# sensor.net
KiCad netlist of a schematic drawn in EAGLE
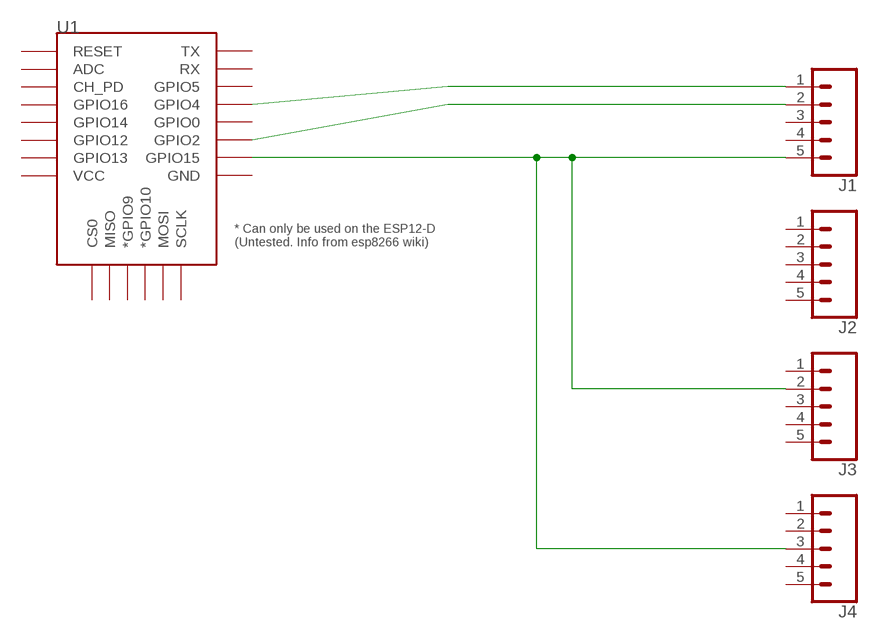
[diagram p0: schematic, sheet 1]

(export (version "E")
  (design (tool "Eeschema 10.0.6"))
  (components
    (comp (ref "J1")
      (value "CONN_05SMD")
      (footprint "eagle-import:1X05_1MM")
      (libsource (lib "eagle-import") (part "CONN_05SMD"))
    )
    (comp (ref "J2")
      (value "CONN_05SMD")
      (footprint "eagle-import:1X05_1MM")
      (libsource (lib "eagle-import") (part "CONN_05SMD"))
    )
    (comp (ref "J3")
      (value "CONN_05SMD")
      (footprint "eagle-import:1X05_1MM")
      (libsource (lib "eagle-import") (part "CONN_05SMD"))
    )
    (comp (ref "J4")
      (value "CONN_05SMD")
      (footprint "eagle-import:1X05_1MM")
      (libsource (lib "eagle-import") (part "CONN_05SMD"))
    )
    (comp (ref "U1")
      (value "ESP12ESMD")
      (footprint "eagle-import:ESP12E-SMD")
      (libsource (lib "eagle-import") (part "ESP12ESMD"))
    )
  )
  (nets
    (net (code "1") (name "Net-(J1-Pad1)") (class "Default")
      (node (ref "J1") (pin "1") (pinfunction "1_1") (pintype "passive"))
      (node (ref "U1") (pin "GPIO4") (pinfunction "GPIO4_GPIO4") (pintype "bidirectional"))
    )
    (net (code "2") (name "Net-(J1-Pad2)") (class "Default")
      (node (ref "J1") (pin "2") (pinfunction "2_2") (pintype "passive"))
      (node (ref "U1") (pin "GPIO2") (pinfunction "GPIO2_GPIO2") (pintype "bidirectional"))
    )
    (net (code "3") (name "Net-(J1-Pad5)") (class "Default")
      (node (ref "J1") (pin "5") (pinfunction "5_5") (pintype "passive"))
      (node (ref "J3") (pin "2") (pinfunction "2_2") (pintype "passive"))
      (node (ref "J4") (pin "3") (pinfunction "3_3") (pintype "passive"))
      (node (ref "U1") (pin "GPIO15") (pinfunction "GPIO15_GPIO15") (pintype "bidirectional"))
    )
    (net (code "4") (name "unconnected-(J1-Pad3)") (class "Default")
      (node (ref "J1") (pin "3") (pinfunction "3_3") (pintype "passive"))
    )
    (net (code "5") (name "unconnected-(J1-Pad4)") (class "Default")
      (node (ref "J1") (pin "4") (pinfunction "4_4") (pintype "passive"))
    )
    (net (code "6") (name "unconnected-(J2-Pad1)") (class "Default")
      (node (ref "J2") (pin "1") (pinfunction "1_1") (pintype "passive"))
    )
    (net (code "7") (name "unconnected-(J2-Pad2)") (class "Default")
      (node (ref "J2") (pin "2") (pinfunction "2_2") (pintype "passive"))
    )
    (net (code "8") (name "unconnected-(J2-Pad3)") (class "Default")
      (node (ref "J2") (pin "3") (pinfunction "3_3") (pintype "passive"))
    )
    (net (code "9") (name "unconnected-(J2-Pad4)") (class "Default")
      (node (ref "J2") (pin "4") (pinfunction "4_4") (pintype "passive"))
    )
    (net (code "10") (name "unconnected-(J2-Pad5)") (class "Default")
      (node (ref "J2") (pin "5") (pinfunction "5_5") (pintype "passive"))
    )
    (net (code "11") (name "unconnected-(J3-Pad1)") (class "Default")
      (node (ref "J3") (pin "1") (pinfunction "1_1") (pintype "passive"))
    )
    (net (code "12") (name "unconnected-(J3-Pad3)") (class "Default")
      (node (ref "J3") (pin "3") (pinfunction "3_3") (pintype "passive"))
    )
    (net (code "13") (name "unconnected-(J3-Pad4)") (class "Default")
      (node (ref "J3") (pin "4") (pinfunction "4_4") (pintype "passive"))
    )
    (net (code "14") (name "unconnected-(J3-Pad5)") (class "Default")
      (node (ref "J3") (pin "5") (pinfunction "5_5") (pintype "passive"))
    )
    (net (code "15") (name "unconnected-(J4-Pad1)") (class "Default")
      (node (ref "J4") (pin "1") (pinfunction "1_1") (pintype "passive"))
    )
    (net (code "16") (name "unconnected-(J4-Pad2)") (class "Default")
      (node (ref "J4") (pin "2") (pinfunction "2_2") (pintype "passive"))
    )
    (net (code "17") (name "unconnected-(J4-Pad4)") (class "Default")
      (node (ref "J4") (pin "4") (pinfunction "4_4") (pintype "passive"))
    )
    (net (code "18") (name "unconnected-(J4-Pad5)") (class "Default")
      (node (ref "J4") (pin "5") (pinfunction "5_5") (pintype "passive"))
    )
    (net (code "19") (name "unconnected-(U1-*GPIO9-PadGPIO9)") (class "Default")
      (node (ref "U1") (pin "GPIO9") (pinfunction "*GPIO9_GPIO9") (pintype "bidirectional"))
    )
    (net (code "20") (name "unconnected-(U1-*GPIO10-PadGPIO10)") (class "Default")
      (node (ref "U1") (pin "GPIO10") (pinfunction "*GPIO10_GPIO10") (pintype "bidirectional"))
    )
    (net (code "21") (name "unconnected-(U1-PadADC)") (class "Default")
      (node (ref "U1") (pin "ADC") (pinfunction "ADC_ADC") (pintype "bidirectional"))
    )
    (net (code "22") (name "unconnected-(U1-PadCH_PD)") (class "Default")
      (node (ref "U1") (pin "CH_PD") (pinfunction "CH_PD_CH_PD") (pintype "bidirectional"))
    )
    (net (code "23") (name "unconnected-(U1-PadCS0)") (class "Default")
      (node (ref "U1") (pin "CS0") (pinfunction "CS0_CS0") (pintype "bidirectional"))
    )
    (net (code "24") (name "unconnected-(U1-PadGND)") (class "Default")
      (node (ref "U1") (pin "GND") (pinfunction "GND_GND") (pintype "bidirectional"))
    )
    (net (code "25") (name "unconnected-(U1-PadGPIO0)") (class "Default")
      (node (ref "U1") (pin "GPIO0") (pinfunction "GPIO0_GPIO0") (pintype "bidirectional"))
    )
    (net (code "26") (name "unconnected-(U1-PadGPIO5)") (class "Default")
      (node (ref "U1") (pin "GPIO5") (pinfunction "GPIO5_GPIO5") (pintype "bidirectional"))
    )
    (net (code "27") (name "unconnected-(U1-PadGPIO12)") (class "Default")
      (node (ref "U1") (pin "GPIO12") (pinfunction "GPIO12_GPIO12") (pintype "bidirectional"))
    )
    (net (code "28") (name "unconnected-(U1-PadGPIO13)") (class "Default")
      (node (ref "U1") (pin "GPIO13") (pinfunction "GPIO13_GPIO13") (pintype "bidirectional"))
    )
    (net (code "29") (name "unconnected-(U1-PadGPIO14)") (class "Default")
      (node (ref "U1") (pin "GPIO14") (pinfunction "GPIO14_GPIO14") (pintype "bidirectional"))
    )
    (net (code "30") (name "unconnected-(U1-PadGPIO16)") (class "Default")
      (node (ref "U1") (pin "GPIO16") (pinfunction "GPIO16_GPIO16") (pintype "bidirectional"))
    )
    (net (code "31") (name "unconnected-(U1-PadMISO)") (class "Default")
      (node (ref "U1") (pin "MISO") (pinfunction "MISO_MISO") (pintype "bidirectional"))
    )
    (net (code "32") (name "unconnected-(U1-PadMOSI)") (class "Default")
      (node (ref "U1") (pin "MOSI") (pinfunction "MOSI_MOSI") (pintype "bidirectional"))
    )
    (net (code "33") (name "unconnected-(U1-PadRESET)") (class "Default")
      (node (ref "U1") (pin "RESET") (pinfunction "RESET_RESET") (pintype "bidirectional"))
    )
    (net (code "34") (name "unconnected-(U1-PadSCLK)") (class "Default")
      (node (ref "U1") (pin "SCLK") (pinfunction "SCLK_SCLK") (pintype "bidirectional"))
    )
    (net (code "35") (name "unconnected-(U1-PadVCC)") (class "Default")
      (node (ref "U1") (pin "VCC") (pinfunction "VCC_VCC") (pintype "bidirectional"))
    )
    (net (code "36") (name "unconnected-(U1-RX-PadRXD0)") (class "Default")
      (node (ref "U1") (pin "RXD0") (pinfunction "RX_RXD0") (pintype "bidirectional"))
    )
    (net (code "37") (name "unconnected-(U1-TX-PadTXD0)") (class "Default")
      (node (ref "U1") (pin "TXD0") (pinfunction "TX_TXD0") (pintype "bidirectional"))
    )
  )
)
